# LPCB220_-_BRAKE_FAILSAFE.net
KiCad netlist of a schematic drawn in Altium Designer
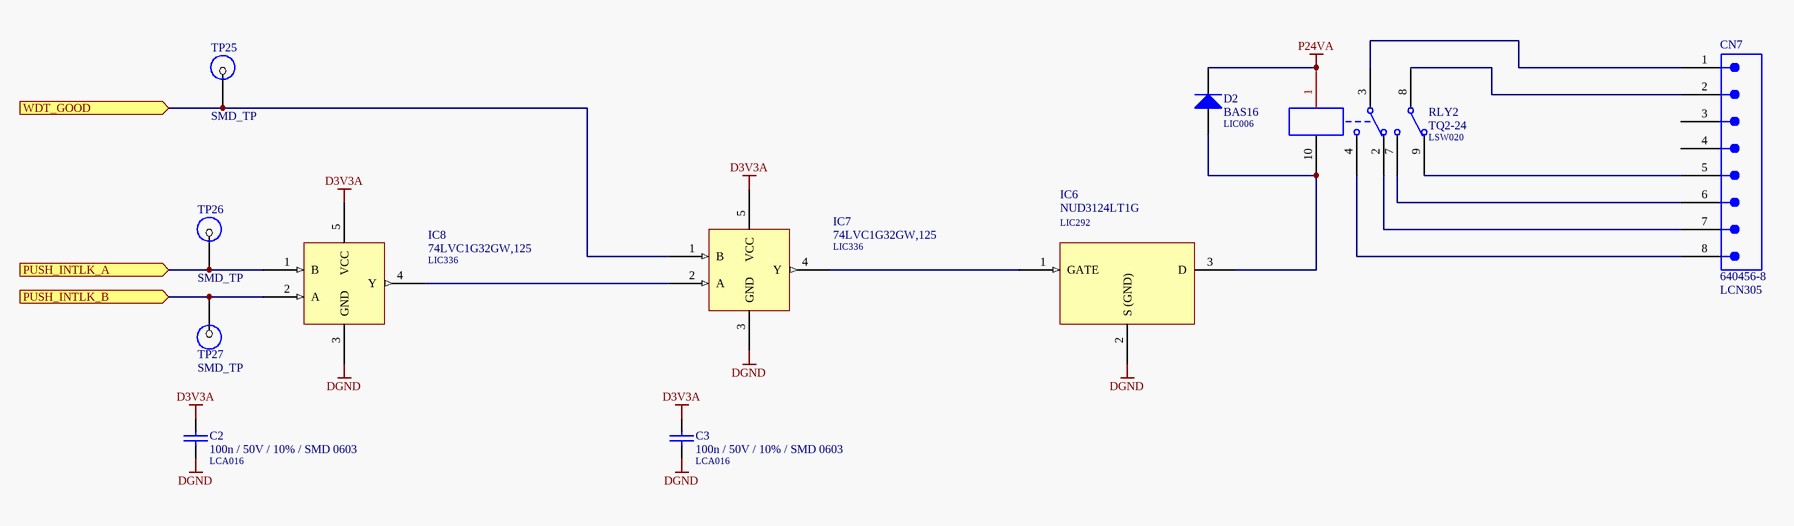
[diagram p0: LPCB220 - BRAKE FAILSAFE.SchDoc]

(export (version "E")
  (design (tool "Eeschema 10.0.6"))
  (components
    (comp (ref "C2")
      (value "100n / 50V / 10% / SMD 0603")
      (footprint "LFP011__CC1608-0603-IPC7351_B")
      (description "Capacitor, Ceramic Chip, 100nF (0.1uF), 50V, 5%, SMD 0603 [LCA016]")
      (fields (field (name "LDL_NUMBER") "LCA016"))
      (libsource (lib "LDL_Capacitors") (part "100n / 50V / 10% / SMD 0603"))
    )
    (comp (ref "C3")
      (value "100n / 50V / 10% / SMD 0603")
      (footprint "LFP011__CC1608-0603-IPC7351_B")
      (description "Capacitor, Ceramic Chip, 100nF (0.1uF), 50V, 5%, SMD 0603 [LCA016]")
      (fields (field (name "LDL_NUMBER") "LCA016"))
      (libsource (lib "LDL_Capacitors") (part "100n / 50V / 10% / SMD 0603"))
    )
    (comp (ref "CN7")
      (value "640456-8")
      (footprint "640456-8")
      (description "Connector, Male Header, 8 Way")
      (fields (field (name "LDL_NUMBER") "LCN305"))
      (libsource (lib "LDL_Connectors") (part "640456-8"))
    )
    (comp (ref "D2")
      (value "BAS16")
      (footprint "LFP021__SOT23")
      (description "Diode, Small Signal, 0.2A, 85V, SMD SOT-23 [LIC006]")
      (fields (field (name "LDL_NUMBER") "LIC006"))
      (libsource (lib "LDL_Semiconductors") (part "BAS16"))
    )
    (comp (ref "IC6")
      (value "NUD3124LT1G")
      (footprint "LFP021__SOT23")
      (description "IC, Relay Driver, 28V Industrial, SMD SOT23 [LIC292]")
      (fields (field (name "LDL_NUMBER") "LIC292"))
      (libsource (lib "LDL_Semiconductors") (part "NUD3124LT1G"))
    )
    (comp (ref "IC7")
      (value "74LVC1G32GW,125")
      (footprint "LFP047__SOT353")
      (description "IC, Logic OR Gate, Single 2 Input, SMD SOT353 [LIC336]")
      (fields (field (name "LDL_NUMBER") "LIC336"))
      (libsource (lib "LDL_Semiconductors") (part "74LVC1G32GW,125"))
    )
    (comp (ref "IC8")
      (value "74LVC1G32GW,125")
      (footprint "LFP047__SOT353")
      (description "IC, Logic OR Gate, Single 2 Input, SMD SOT353 [LIC336]")
      (fields (field (name "LDL_NUMBER") "LIC336"))
      (libsource (lib "LDL_Semiconductors") (part "74LVC1G32GW,125"))
    )
    (comp (ref "RLY2")
      (value "TQ2-24")
      (footprint "TQ2")
      (description "Relay, DPDT, Non Latching, 24VDC Coil, 1A Rating, PTH")
      (fields (field (name "LDL_NUMBER") "LSW020"))
      (libsource (lib "LDL_Switching") (part "TQ2-24"))
    )
    (comp (ref "TP25")
      (value "SMD_TP")
      (footprint "SMD-TP")
      (description "SMD Test Point")
      (libsource (lib "LDL_Connectors") (part "SMD_TP"))
    )
    (comp (ref "TP26")
      (value "SMD_TP")
      (footprint "SMD-TP")
      (description "SMD Test Point")
      (libsource (lib "LDL_Connectors") (part "SMD_TP"))
    )
    (comp (ref "TP27")
      (value "SMD_TP")
      (footprint "SMD-TP")
      (description "SMD Test Point")
      (libsource (lib "LDL_Connectors") (part "SMD_TP"))
    )
  )
  (nets
    (net (code "1") (name "/PUSH_INTLK_A") (class "Default")
      (node (ref "IC8") (pin "1") (pinfunction "B_1") (pintype "input"))
      (node (ref "TP26") (pin "1") (pintype "passive"))
    )
    (net (code "2") (name "/PUSH_INTLK_B") (class "Default")
      (node (ref "IC8") (pin "2") (pinfunction "A_2") (pintype "input"))
      (node (ref "TP27") (pin "1") (pintype "passive"))
    )
    (net (code "3") (name "/WDT_GOOD") (class "Default")
      (node (ref "IC7") (pin "1") (pinfunction "B_1") (pintype "input"))
      (node (ref "TP25") (pin "1") (pintype "passive"))
    )
    (net (code "4") (name "D3V3A") (class "Default")
      (node (ref "C2") (pin "1") (pintype "passive"))
      (node (ref "C3") (pin "1") (pintype "passive"))
      (node (ref "IC7") (pin "5") (pinfunction "VCC_5") (pintype "power_in"))
      (node (ref "IC8") (pin "5") (pinfunction "VCC_5") (pintype "power_in"))
    )
    (net (code "5") (name "DGND") (class "Default")
      (node (ref "C2") (pin "2") (pintype "passive"))
      (node (ref "C3") (pin "2") (pintype "passive"))
      (node (ref "IC6") (pin "2") (pinfunction "S_(GND)_2") (pintype "passive"))
      (node (ref "IC7") (pin "3") (pinfunction "GND_3") (pintype "power_in"))
      (node (ref "IC8") (pin "3") (pinfunction "GND_3") (pintype "power_in"))
    )
    (net (code "6") (name "Net-(CN7-Pad1)") (class "Default")
      (node (ref "CN7") (pin "1") (pinfunction "1_1") (pintype "passive"))
      (node (ref "RLY2") (pin "3") (pinfunction "3_3") (pintype "passive"))
    )
    (net (code "7") (name "Net-(CN7-Pad2)") (class "Default")
      (node (ref "CN7") (pin "2") (pinfunction "2_2") (pintype "passive"))
      (node (ref "RLY2") (pin "8") (pinfunction "8_8") (pintype "passive"))
    )
    (net (code "8") (name "Net-(CN7-Pad5)") (class "Default")
      (node (ref "CN7") (pin "5") (pinfunction "5_5") (pintype "passive"))
      (node (ref "RLY2") (pin "9") (pinfunction "9_9") (pintype "passive"))
    )
    (net (code "9") (name "Net-(CN7-Pad6)") (class "Default")
      (node (ref "CN7") (pin "6") (pinfunction "6_6") (pintype "passive"))
      (node (ref "RLY2") (pin "7") (pinfunction "7_7") (pintype "passive"))
    )
    (net (code "10") (name "Net-(CN7-Pad7)") (class "Default")
      (node (ref "CN7") (pin "7") (pinfunction "7_7") (pintype "passive"))
      (node (ref "RLY2") (pin "2") (pinfunction "2_2") (pintype "passive"))
    )
    (net (code "11") (name "Net-(CN7-Pad8)") (class "Default")
      (node (ref "CN7") (pin "8") (pinfunction "8_8") (pintype "passive"))
      (node (ref "RLY2") (pin "4") (pinfunction "4_4") (pintype "passive"))
    )
    (net (code "12") (name "Net-(D2-A)") (class "Default")
      (node (ref "D2") (pin "1") (pinfunction "A_1") (pintype "passive"))
      (node (ref "IC6") (pin "3") (pinfunction "D_3") (pintype "passive"))
      (node (ref "RLY2") (pin "10") (pinfunction "10_10") (pintype "passive"))
    )
    (net (code "13") (name "Net-(IC6-GATE)") (class "Default")
      (node (ref "IC6") (pin "1") (pinfunction "GATE_1") (pintype "input"))
      (node (ref "IC7") (pin "4") (pinfunction "Y_4") (pintype "output"))
    )
    (net (code "14") (name "Net-(IC7-A)") (class "Default")
      (node (ref "IC7") (pin "2") (pinfunction "A_2") (pintype "input"))
      (node (ref "IC8") (pin "4") (pinfunction "Y_4") (pintype "output"))
    )
    (net (code "15") (name "P24VA") (class "Default")
      (node (ref "D2") (pin "3") (pinfunction "K_3") (pintype "passive"))
      (node (ref "RLY2") (pin "1") (pinfunction "1_1") (pintype "passive"))
    )
    (net (code "16") (name "unconnected-(CN7-Pad3)") (class "Default")
      (node (ref "CN7") (pin "3") (pinfunction "3_3") (pintype "passive"))
    )
    (net (code "17") (name "unconnected-(CN7-Pad4)") (class "Default")
      (node (ref "CN7") (pin "4") (pinfunction "4_4") (pintype "passive"))
    )
  )
)
